# Push_Buttons.net
KiCad netlist of a schematic drawn in Altium Designer
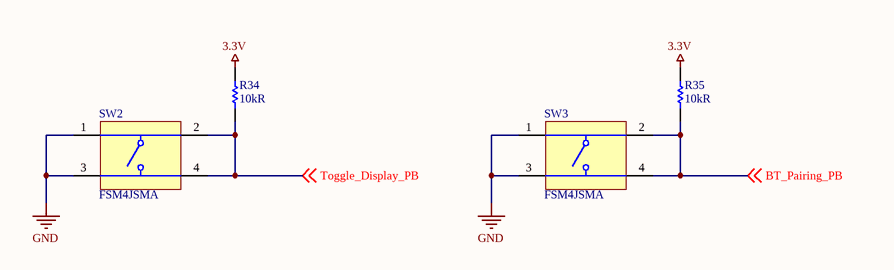
[diagram p0: Push_Buttons.SchDoc]

(export (version "E")
  (design (tool "Eeschema 10.0.6"))
  (components
    (comp (ref "R34")
      (value "RC0805FR-0710KL")
      (footprint "RESC2013X60X35NL10T20")
      (description "Chip Resistor, 10 KOhm, +/- 1%, 0.125 W, -55 to 155 degC, 0805 (2012 Metric), RoHS, Tape and Reel")
      (fields
        (field (name "MANUFACTURER") "Yageo")
        (field (name "RESISTANCE") "10kR")
        (field (name "TOLERANCE") "1%")
      )
      (libsource (lib "Altium Content Vault") (part "RES-2"))
    )
    (comp (ref "R35")
      (value "RC0805FR-0710KL")
      (footprint "RESC2013X60X35NL10T20")
      (description "Chip Resistor, 10 KOhm, +/- 1%, 0.125 W, -55 to 155 degC, 0805 (2012 Metric), RoHS, Tape and Reel")
      (fields
        (field (name "MANUFACTURER") "Yageo")
        (field (name "RESISTANCE") "10kR")
        (field (name "TOLERANCE") "1%")
      )
      (libsource (lib "Altium Content Vault") (part "RES-2"))
    )
    (comp (ref "SW2")
      (value "FSM4JSMA")
      (footprint "TECO-FSM4JSMA_V")
      (description "Swicth, SPST, 24 V, -35 to 85 degC, 4-Pin SMD, RoHS, Tape and Reel")
      (fields (field (name "MANUFACTURER") "TE Connectivity"))
      (libsource (lib "Altium Content Vault") (part "SW-SPST-4_A"))
    )
    (comp (ref "SW3")
      (value "FSM4JSMA")
      (footprint "TECO-FSM4JSMA_V")
      (description "Swicth, SPST, 24 V, -35 to 85 degC, 4-Pin SMD, RoHS, Tape and Reel")
      (fields (field (name "MANUFACTURER") "TE Connectivity"))
      (libsource (lib "Altium Content Vault") (part "SW-SPST-4_A"))
    )
  )
  (nets
    (net (code "1") (name "3.3V") (class "Default")
      (node (ref "R34") (pin "2") (pinfunction "2_2") (pintype "passive"))
      (node (ref "R35") (pin "2") (pinfunction "2_2") (pintype "passive"))
    )
    (net (code "2") (name "BT_Pairing_PB") (class "Default")
      (node (ref "R35") (pin "1") (pinfunction "1_1") (pintype "passive"))
      (node (ref "SW3") (pin "2") (pinfunction "2_2") (pintype "passive"))
      (node (ref "SW3") (pin "4") (pinfunction "4_4") (pintype "passive"))
    )
    (net (code "3") (name "GND") (class "Default")
      (node (ref "SW2") (pin "1") (pinfunction "1_1") (pintype "passive"))
      (node (ref "SW2") (pin "3") (pinfunction "3_3") (pintype "passive"))
      (node (ref "SW3") (pin "1") (pinfunction "1_1") (pintype "passive"))
      (node (ref "SW3") (pin "3") (pinfunction "3_3") (pintype "passive"))
    )
    (net (code "4") (name "Toggle_Display_PB") (class "Default")
      (node (ref "R34") (pin "1") (pinfunction "1_1") (pintype "passive"))
      (node (ref "SW2") (pin "2") (pinfunction "2_2") (pintype "passive"))
      (node (ref "SW2") (pin "4") (pinfunction "4_4") (pintype "passive"))
    )
  )
)
